# 2_STM32_Tutorial-MCU.net
KiCad netlist of a schematic drawn in Altium Designer
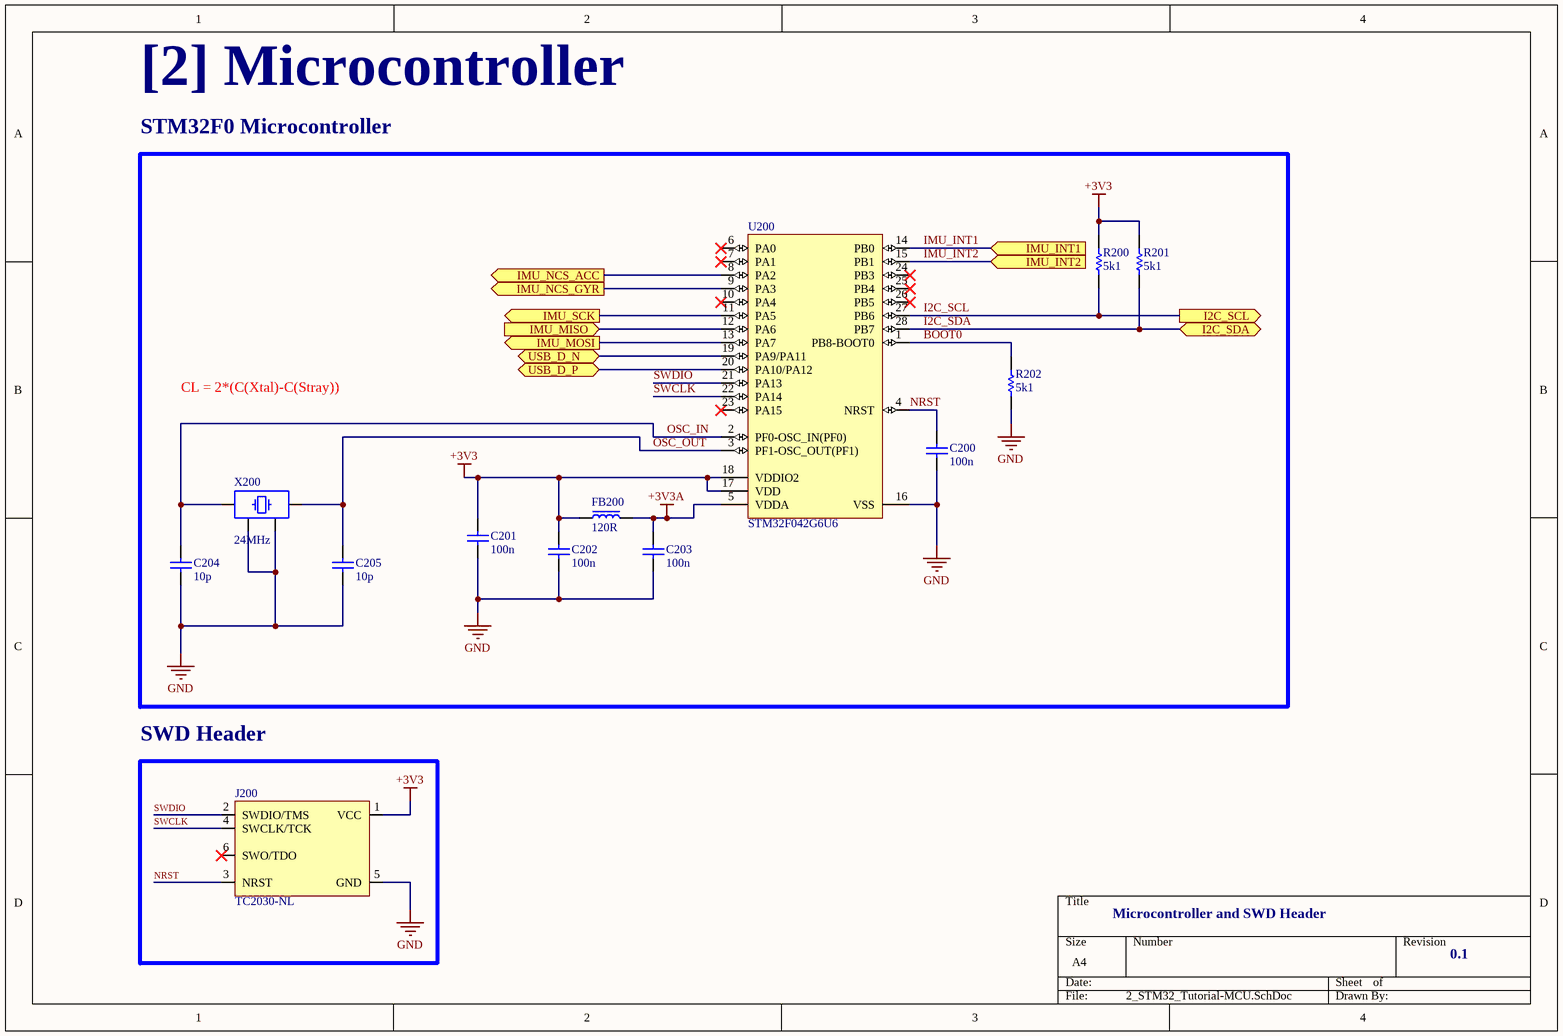
[diagram p0: 2_STM32_Tutorial-MCU.SchDoc]

(export (version "E")
  (design (tool "Eeschema 10.0.6"))
  (components
    (comp (ref "C200")
      (value "100n")
      (footprint "CAP_0603")
      (description "Capacitor SMD 0603 Generic")
      (libsource (lib "AndreiLib") (part "CAP_0603"))
    )
    (comp (ref "C201")
      (value "100n")
      (footprint "CAP_0603")
      (description "Capacitor SMD 0603 Generic")
      (libsource (lib "AndreiLib") (part "CAP_0603"))
    )
    (comp (ref "C202")
      (value "100n")
      (footprint "CAP_0603")
      (description "Capacitor SMD 0603 Generic")
      (libsource (lib "AndreiLib") (part "CAP_0603"))
    )
    (comp (ref "C203")
      (value "100n")
      (footprint "CAP_0603")
      (description "Capacitor SMD 0603 Generic")
      (libsource (lib "AndreiLib") (part "CAP_0603"))
    )
    (comp (ref "C204")
      (value "10p")
      (footprint "CAP_0603")
      (description "Capacitor SMD 0603 Generic")
      (libsource (lib "AndreiLib") (part "CAP_0603"))
    )
    (comp (ref "C205")
      (value "10p")
      (footprint "CAP_0603")
      (description "Capacitor SMD 0603 Generic")
      (libsource (lib "AndreiLib") (part "CAP_0603"))
    )
    (comp (ref "FB200")
      (value "120R")
      (footprint "KMZ1608DHR121CTDH5")
      (description "Ferrite Beads 120MHz 0.3Ohm 25% 1608 AEC-Q200")
      (libsource (lib "AndreiLib") (part "KMZ1608DHR121CTDH5"))
    )
    (comp (ref "J200")
      (value "TC2030-NL")
      (footprint "TC2030-NL-FP")
      (description "Tag-Connect No-Solder SWD Debug Connector (No Legs) DO NOT PLACE")
      (fields
        (field (name "MANUFACTURER") "Tag-Connect")
        (field (name "MANUFACTURER PART NUMBER") "TC2030-NL-FP")
      )
      (libsource (lib "AndreiLib") (part "TC2030-NL"))
    )
    (comp (ref "R200")
      (value "5k1")
      (footprint "RES_0603")
      (description "Resistor SMD 0603 Generic")
      (libsource (lib "AndreiLib") (part "RES_0603"))
    )
    (comp (ref "R201")
      (value "5k1")
      (footprint "RES_0603")
      (description "Resistor SMD 0603 Generic")
      (libsource (lib "AndreiLib") (part "RES_0603"))
    )
    (comp (ref "R202")
      (value "5k1")
      (footprint "RES_0603")
      (description "Resistor SMD 0603 Generic")
      (libsource (lib "AndreiLib") (part "RES_0603"))
    )
    (comp (ref "U200")
      (value "STM32F042G6U6")
      (footprint "STM-UFQFPN28_V")
      (fields (field (name "MANUFACTURER") "STMicroelectronics"))
      (libsource (lib "Altium Content Vault") (part "MC-ARM-STM32F042-UFQFPN28"))
    )
    (comp (ref "X200")
      (value "24MHz")
      (footprint "TSX-3225_24.0000MF15X-AC")
      (description "Crystal SMD 24MHz 10PPM 7pF 3225")
      (fields
        (field (name "MANUFACTURER") "Epson")
        (field (name "MANUFACTURER PART NUMBER") "TSX-3225_24.0000MF15X-AC")
      )
      (libsource (lib "AndreiLib") (part "TSX-3225_24.0000MF15X-AC"))
    )
  )
  (nets
    (net (code "1") (name "+3V3") (class "Default")
      (node (ref "C201") (pin "2") (pintype "passive"))
      (node (ref "C202") (pin "2") (pintype "passive"))
      (node (ref "FB200") (pin "1") (pinfunction "1_1") (pintype "passive"))
      (node (ref "J200") (pin "1") (pinfunction "VCC_1") (pintype "passive"))
      (node (ref "R200") (pin "2") (pintype "passive"))
      (node (ref "R201") (pin "2") (pintype "passive"))
      (node (ref "U200") (pin "17") (pinfunction "VDD_17") (pintype "power_in"))
      (node (ref "U200") (pin "18") (pinfunction "VDDIO2_18") (pintype "power_in"))
    )
    (net (code "2") (name "+3V3A") (class "Default")
      (node (ref "C203") (pin "2") (pintype "passive"))
      (node (ref "FB200") (pin "2") (pinfunction "2_2") (pintype "passive"))
      (node (ref "U200") (pin "5") (pinfunction "VDDA_5") (pintype "power_in"))
    )
    (net (code "3") (name "/BOOT0") (class "Default")
      (node (ref "R202") (pin "2") (pintype "passive"))
      (node (ref "U200") (pin "1") (pinfunction "PB8-BOOT0_1") (pintype "bidirectional"))
    )
    (net (code "4") (name "/I2C_SCL") (class "Default")
      (node (ref "R200") (pin "1") (pintype "passive"))
      (node (ref "U200") (pin "27") (pinfunction "PB6_27") (pintype "bidirectional"))
    )
    (net (code "5") (name "/I2C_SDA") (class "Default")
      (node (ref "R201") (pin "1") (pintype "passive"))
      (node (ref "U200") (pin "28") (pinfunction "PB7_28") (pintype "bidirectional"))
    )
    (net (code "6") (name "/IMU_INT1") (class "Default")
      (node (ref "U200") (pin "14") (pinfunction "PB0_14") (pintype "bidirectional"))
    )
    (net (code "7") (name "/IMU_INT2") (class "Default")
      (node (ref "U200") (pin "15") (pinfunction "PB1_15") (pintype "bidirectional"))
    )
    (net (code "8") (name "/IMU_MISO") (class "Default")
      (node (ref "U200") (pin "12") (pinfunction "PA6_12") (pintype "bidirectional"))
    )
    (net (code "9") (name "/IMU_MOSI") (class "Default")
      (node (ref "U200") (pin "13") (pinfunction "PA7_13") (pintype "bidirectional"))
    )
    (net (code "10") (name "/IMU_NCS_ACC") (class "Default")
      (node (ref "U200") (pin "8") (pinfunction "PA2_8") (pintype "bidirectional"))
    )
    (net (code "11") (name "/IMU_NCS_GYR") (class "Default")
      (node (ref "U200") (pin "9") (pinfunction "PA3_9") (pintype "bidirectional"))
    )
    (net (code "12") (name "/IMU_SCK") (class "Default")
      (node (ref "U200") (pin "11") (pinfunction "PA5_11") (pintype "bidirectional"))
    )
    (net (code "13") (name "/NRST") (class "Default")
      (node (ref "C200") (pin "2") (pintype "passive"))
      (node (ref "J200") (pin "3") (pinfunction "NRST_3") (pintype "passive"))
      (node (ref "U200") (pin "4") (pinfunction "NRST_4") (pintype "bidirectional"))
    )
    (net (code "14") (name "/OSC_IN") (class "Default")
      (node (ref "C204") (pin "2") (pintype "passive"))
      (node (ref "U200") (pin "2") (pinfunction "PF0-OSC_IN(PF0)_2") (pintype "bidirectional"))
      (node (ref "X200") (pin "1") (pinfunction "1_1") (pintype "passive"))
    )
    (net (code "15") (name "/OSC_OUT") (class "Default")
      (node (ref "C205") (pin "2") (pintype "passive"))
      (node (ref "U200") (pin "3") (pinfunction "PF1-OSC_OUT(PF1)_3") (pintype "bidirectional"))
      (node (ref "X200") (pin "3") (pinfunction "3_3") (pintype "passive"))
    )
    (net (code "16") (name "/SWCLK") (class "Default")
      (node (ref "J200") (pin "4") (pinfunction "SWCLK/TCK_4") (pintype "passive"))
      (node (ref "U200") (pin "22") (pinfunction "PA14_22") (pintype "bidirectional"))
    )
    (net (code "17") (name "/SWDIO") (class "Default")
      (node (ref "J200") (pin "2") (pinfunction "SWDIO/TMS_2") (pintype "passive"))
      (node (ref "U200") (pin "21") (pinfunction "PA13_21") (pintype "bidirectional"))
    )
    (net (code "18") (name "/USB_D_N") (class "Default")
      (node (ref "U200") (pin "19") (pinfunction "PA9/PA11_19") (pintype "bidirectional"))
    )
    (net (code "19") (name "/USB_D_P") (class "Default")
      (node (ref "U200") (pin "20") (pinfunction "PA10/PA12_20") (pintype "bidirectional"))
    )
    (net (code "20") (name "GND") (class "Default")
      (node (ref "C200") (pin "1") (pintype "passive"))
      (node (ref "C201") (pin "1") (pintype "passive"))
      (node (ref "C202") (pin "1") (pintype "passive"))
      (node (ref "C203") (pin "1") (pintype "passive"))
      (node (ref "C204") (pin "1") (pintype "passive"))
      (node (ref "C205") (pin "1") (pintype "passive"))
      (node (ref "J200") (pin "5") (pinfunction "GND_5") (pintype "passive"))
      (node (ref "R202") (pin "1") (pintype "passive"))
      (node (ref "U200") (pin "16") (pinfunction "VSS_16") (pintype "power_in"))
      (node (ref "X200") (pin "2") (pinfunction "2_2") (pintype "passive"))
      (node (ref "X200") (pin "4") (pinfunction "4_4") (pintype "passive"))
    )
    (net (code "21") (name "unconnected-(J200-SWO{slash}TDO-Pad6)") (class "Default")
      (node (ref "J200") (pin "6") (pinfunction "SWO/TDO_6") (pintype "passive+no_connect"))
    )
    (net (code "22") (name "unconnected-(U200-PA0-Pad6)") (class "Default")
      (node (ref "U200") (pin "6") (pinfunction "PA0_6") (pintype "bidirectional+no_connect"))
    )
    (net (code "23") (name "unconnected-(U200-PA1-Pad7)") (class "Default")
      (node (ref "U200") (pin "7") (pinfunction "PA1_7") (pintype "bidirectional+no_connect"))
    )
    (net (code "24") (name "unconnected-(U200-PA4-Pad10)") (class "Default")
      (node (ref "U200") (pin "10") (pinfunction "PA4_10") (pintype "bidirectional+no_connect"))
    )
    (net (code "25") (name "unconnected-(U200-PA15-Pad23)") (class "Default")
      (node (ref "U200") (pin "23") (pinfunction "PA15_23") (pintype "bidirectional+no_connect"))
    )
    (net (code "26") (name "unconnected-(U200-PB3-Pad24)") (class "Default")
      (node (ref "U200") (pin "24") (pinfunction "PB3_24") (pintype "bidirectional+no_connect"))
    )
    (net (code "27") (name "unconnected-(U200-PB4-Pad25)") (class "Default")
      (node (ref "U200") (pin "25") (pinfunction "PB4_25") (pintype "bidirectional+no_connect"))
    )
    (net (code "28") (name "unconnected-(U200-PB5-Pad26)") (class "Default")
      (node (ref "U200") (pin "26") (pinfunction "PB5_26") (pintype "bidirectional+no_connect"))
    )
  )
)
